# Xonik_Waveshaper_v1_0_w_gp.net
KiCad netlist of a schematic drawn in EAGLE
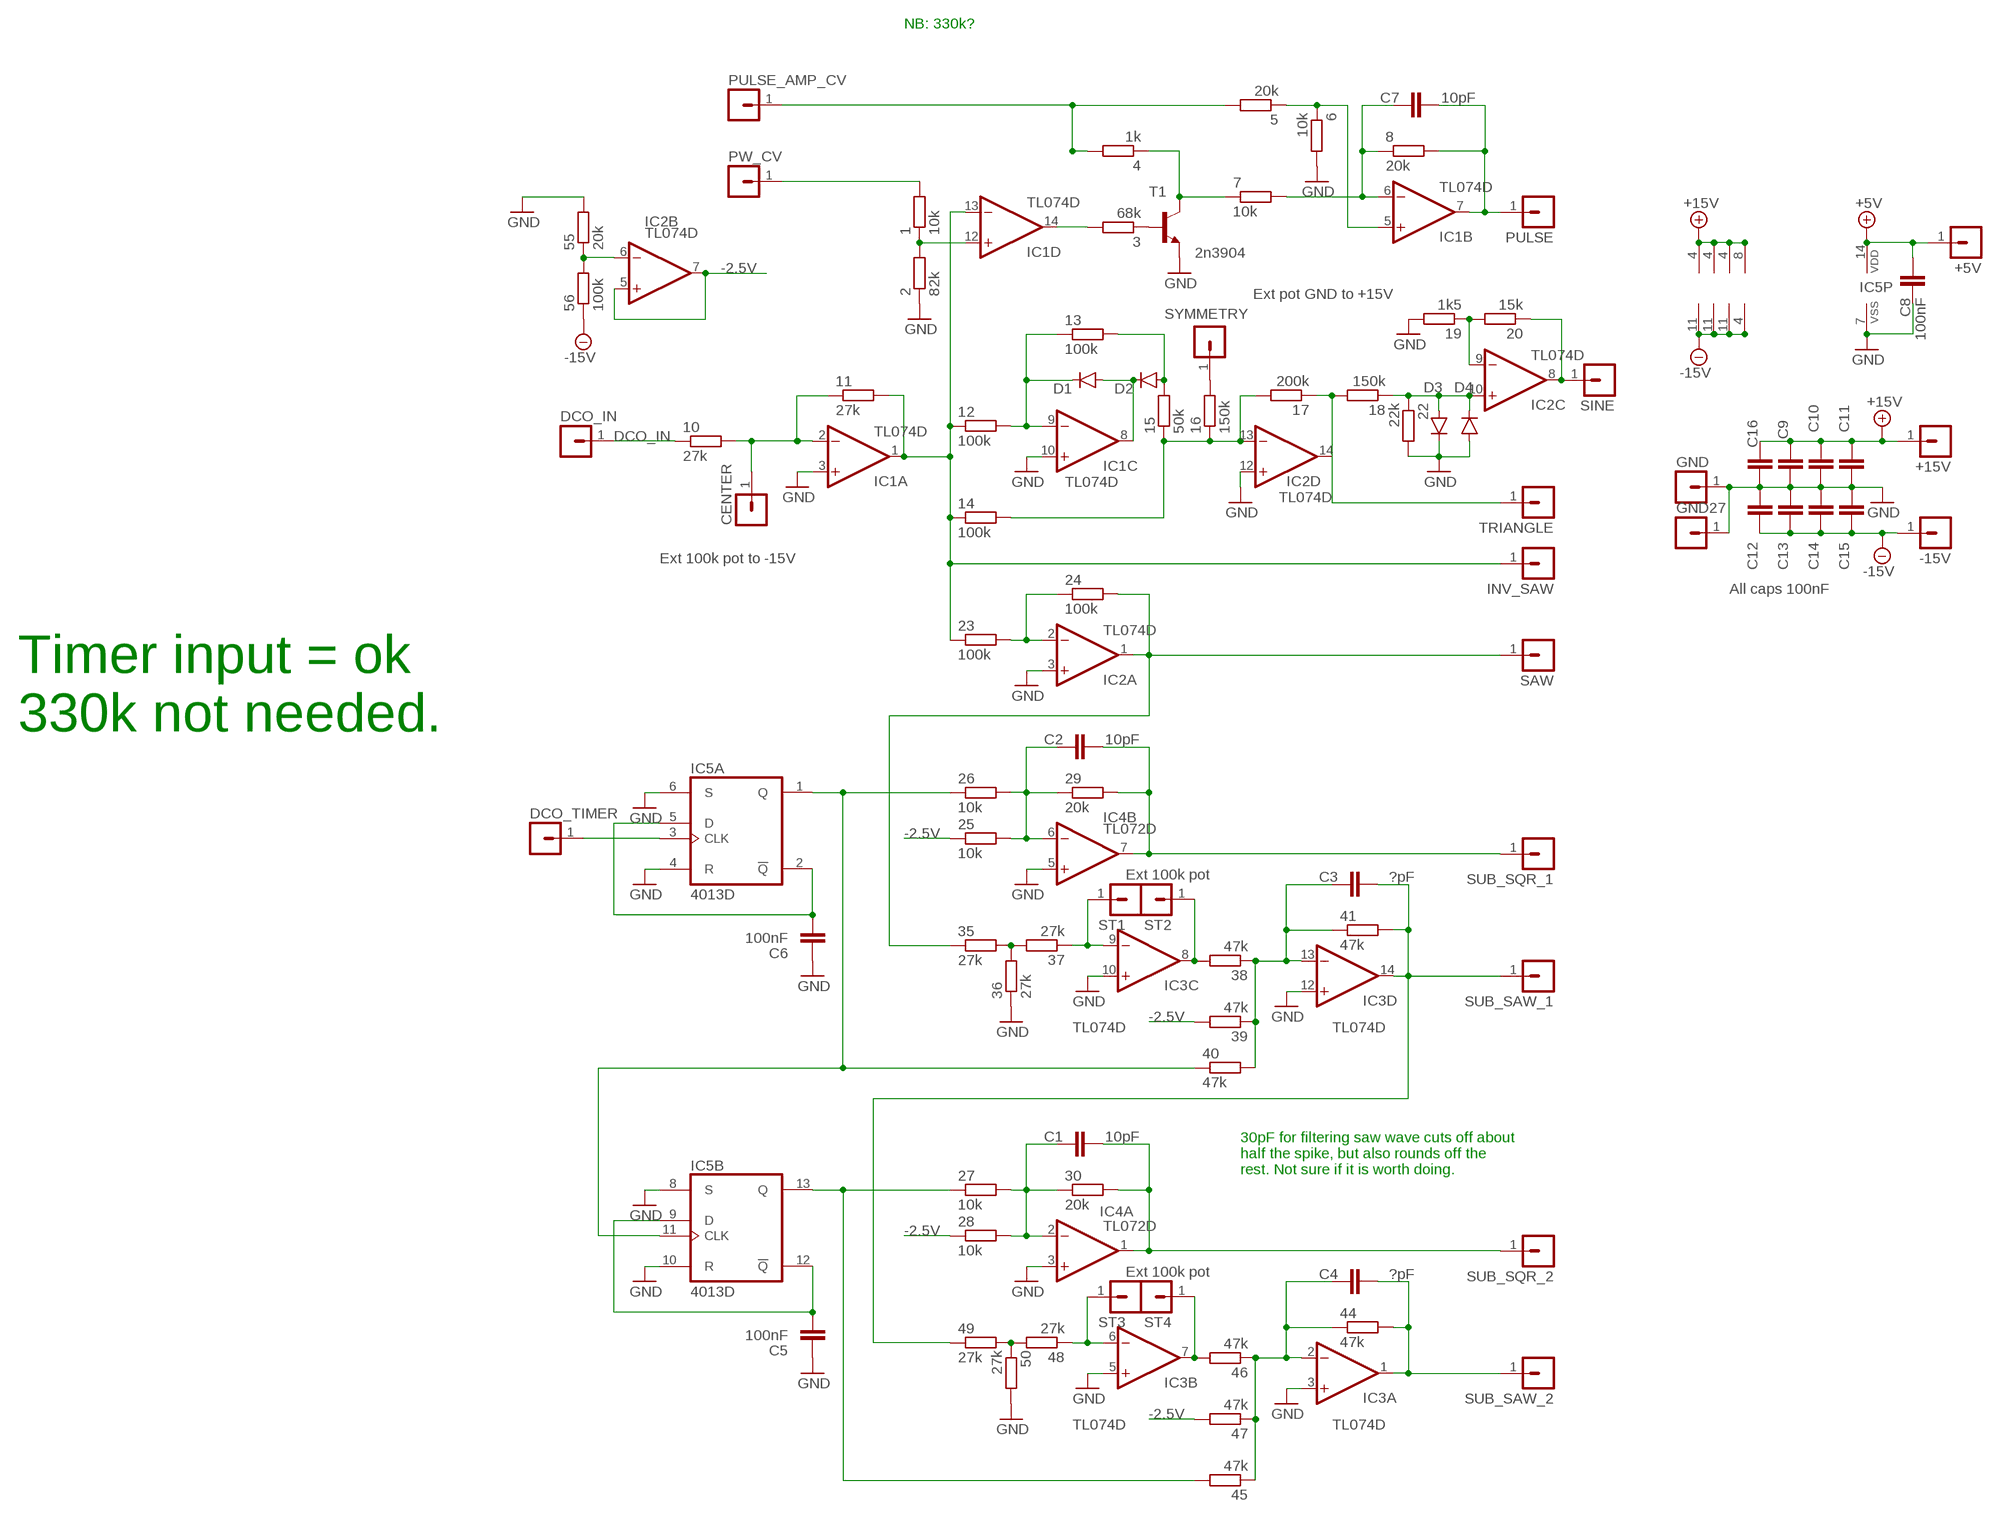
[diagram p0: schematic, sheet 1]

(export (version "E")
  (design (tool "Eeschema 10.0.6"))
  (components
    (comp (ref "+5V")
      (value "MA01-1JP")
      (footprint "eagle-import:SIP-PIN01-1J")
      (libsource (lib "eagle-import") (part "MA01-1JP"))
    )
    (comp (ref "+15V")
      (value "MA01-1JP")
      (footprint "eagle-import:SIP-PIN01-1J")
      (libsource (lib "eagle-import") (part "MA01-1JP"))
    )
    (comp (ref "-15V")
      (value "MA01-1JP")
      (footprint "eagle-import:SIP-PIN01-1J")
      (libsource (lib "eagle-import") (part "MA01-1JP"))
    )
    (comp (ref "1")
      (value "10k")
      (footprint "eagle-import:R0805")
      (libsource (lib "eagle-import") (part "R-EU_R0805"))
    )
    (comp (ref "2")
      (value "82k")
      (footprint "eagle-import:R0805")
      (libsource (lib "eagle-import") (part "R-EU_R0805"))
    )
    (comp (ref "3")
      (value "68k")
      (footprint "eagle-import:R0805")
      (libsource (lib "eagle-import") (part "R-EU_R0805"))
    )
    (comp (ref "4")
      (value "1k")
      (footprint "eagle-import:R0805")
      (libsource (lib "eagle-import") (part "R-EU_R0805"))
    )
    (comp (ref "5")
      (value "20k")
      (footprint "eagle-import:R0805")
      (libsource (lib "eagle-import") (part "R-EU_R0805"))
    )
    (comp (ref "6")
      (value "10k")
      (footprint "eagle-import:R0805")
      (libsource (lib "eagle-import") (part "R-EU_R0805"))
    )
    (comp (ref "7")
      (value "10k")
      (footprint "eagle-import:R0805")
      (libsource (lib "eagle-import") (part "R-EU_R0805"))
    )
    (comp (ref "8")
      (value "20k")
      (footprint "eagle-import:R0805")
      (libsource (lib "eagle-import") (part "R-EU_R0805"))
    )
    (comp (ref "10")
      (value "27k")
      (footprint "eagle-import:R0805")
      (libsource (lib "eagle-import") (part "R-EU_R0805"))
    )
    (comp (ref "11")
      (value "27k")
      (footprint "eagle-import:R0805")
      (libsource (lib "eagle-import") (part "R-EU_R0805"))
    )
    (comp (ref "12")
      (value "100k")
      (footprint "eagle-import:R0805")
      (libsource (lib "eagle-import") (part "R-EU_R0805"))
    )
    (comp (ref "13")
      (value "100k")
      (footprint "eagle-import:R0805")
      (libsource (lib "eagle-import") (part "R-EU_R0805"))
    )
    (comp (ref "14")
      (value "100k")
      (footprint "eagle-import:R0805")
      (libsource (lib "eagle-import") (part "R-EU_R0805"))
    )
    (comp (ref "15")
      (value "50k")
      (footprint "eagle-import:R0805")
      (libsource (lib "eagle-import") (part "R-EU_R0805"))
    )
    (comp (ref "16")
      (value "150k")
      (footprint "eagle-import:R0805")
      (libsource (lib "eagle-import") (part "R-EU_R0805"))
    )
    (comp (ref "17")
      (value "200k")
      (footprint "eagle-import:R0805")
      (libsource (lib "eagle-import") (part "R-EU_R0805"))
    )
    (comp (ref "18")
      (value "150k")
      (footprint "eagle-import:R0805")
      (libsource (lib "eagle-import") (part "R-EU_R0805"))
    )
    (comp (ref "19")
      (value "1k5")
      (footprint "eagle-import:R0805")
      (libsource (lib "eagle-import") (part "R-EU_R0805"))
    )
    (comp (ref "20")
      (value "15k")
      (footprint "eagle-import:R0805")
      (libsource (lib "eagle-import") (part "R-EU_R0805"))
    )
    (comp (ref "22")
      (value "22k")
      (footprint "eagle-import:R0805")
      (libsource (lib "eagle-import") (part "R-EU_R0805"))
    )
    (comp (ref "23")
      (value "100k")
      (footprint "eagle-import:R0805")
      (libsource (lib "eagle-import") (part "R-EU_R0805"))
    )
    (comp (ref "24")
      (value "100k")
      (footprint "eagle-import:R0805")
      (libsource (lib "eagle-import") (part "R-EU_R0805"))
    )
    (comp (ref "25")
      (value "10k")
      (footprint "eagle-import:R0805")
      (libsource (lib "eagle-import") (part "R-EU_R0805"))
    )
    (comp (ref "26")
      (value "10k")
      (footprint "eagle-import:R0805")
      (libsource (lib "eagle-import") (part "R-EU_R0805"))
    )
    (comp (ref "27")
      (value "10k")
      (footprint "eagle-import:R0805")
      (libsource (lib "eagle-import") (part "R-EU_R0805"))
    )
    (comp (ref "28")
      (value "10k")
      (footprint "eagle-import:R0805")
      (libsource (lib "eagle-import") (part "R-EU_R0805"))
    )
    (comp (ref "29")
      (value "20k")
      (footprint "eagle-import:R0805")
      (libsource (lib "eagle-import") (part "R-EU_R0805"))
    )
    (comp (ref "30")
      (value "20k")
      (footprint "eagle-import:R0805")
      (libsource (lib "eagle-import") (part "R-EU_R0805"))
    )
    (comp (ref "35")
      (value "27k")
      (footprint "eagle-import:R0805")
      (libsource (lib "eagle-import") (part "R-EU_R0805"))
    )
    (comp (ref "36")
      (value "27k")
      (footprint "eagle-import:R0805")
      (libsource (lib "eagle-import") (part "R-EU_R0805"))
    )
    (comp (ref "37")
      (value "27k")
      (footprint "eagle-import:R0805")
      (libsource (lib "eagle-import") (part "R-EU_R0805"))
    )
    (comp (ref "38")
      (value "47k")
      (footprint "eagle-import:R0805")
      (libsource (lib "eagle-import") (part "R-EU_R0805"))
    )
    (comp (ref "39")
      (value "47k")
      (footprint "eagle-import:R0805")
      (libsource (lib "eagle-import") (part "R-EU_R0805"))
    )
    (comp (ref "40")
      (value "47k")
      (footprint "eagle-import:R0805")
      (libsource (lib "eagle-import") (part "R-EU_R0805"))
    )
    (comp (ref "41")
      (value "47k")
      (footprint "eagle-import:R0805")
      (libsource (lib "eagle-import") (part "R-EU_R0805"))
    )
    (comp (ref "44")
      (value "47k")
      (footprint "eagle-import:R0805")
      (libsource (lib "eagle-import") (part "R-EU_R0805"))
    )
    (comp (ref "45")
      (value "47k")
      (footprint "eagle-import:R0805")
      (libsource (lib "eagle-import") (part "R-EU_R0805"))
    )
    (comp (ref "46")
      (value "47k")
      (footprint "eagle-import:R0805")
      (libsource (lib "eagle-import") (part "R-EU_R0805"))
    )
    (comp (ref "47")
      (value "47k")
      (footprint "eagle-import:R0805")
      (libsource (lib "eagle-import") (part "R-EU_R0805"))
    )
    (comp (ref "48")
      (value "27k")
      (footprint "eagle-import:R0805")
      (libsource (lib "eagle-import") (part "R-EU_R0805"))
    )
    (comp (ref "49")
      (value "27k")
      (footprint "eagle-import:R0805")
      (libsource (lib "eagle-import") (part "R-EU_R0805"))
    )
    (comp (ref "50")
      (value "27k")
      (footprint "eagle-import:R0805")
      (libsource (lib "eagle-import") (part "R-EU_R0805"))
    )
    (comp (ref "55")
      (value "20k")
      (footprint "eagle-import:R0805")
      (libsource (lib "eagle-import") (part "R-EU_R0805"))
    )
    (comp (ref "56")
      (value "100k")
      (footprint "eagle-import:R0805")
      (libsource (lib "eagle-import") (part "R-EU_R0805"))
    )
    (comp (ref "C1")
      (value "10pF")
      (footprint "eagle-import:C0805")
      (libsource (lib "eagle-import") (part "C-EUC0805"))
    )
    (comp (ref "C2")
      (value "10pF")
      (footprint "eagle-import:C0805")
      (libsource (lib "eagle-import") (part "C-EUC0805"))
    )
    (comp (ref "C3")
      (value "?pF")
      (footprint "eagle-import:C0805")
      (libsource (lib "eagle-import") (part "C-EUC0805"))
    )
    (comp (ref "C4")
      (value "?pF")
      (footprint "eagle-import:C0805")
      (libsource (lib "eagle-import") (part "C-EUC0805"))
    )
    (comp (ref "C5")
      (value "100nF")
      (footprint "eagle-import:C0805")
      (libsource (lib "eagle-import") (part "C-EUC0805"))
    )
    (comp (ref "C6")
      (value "100nF")
      (footprint "eagle-import:C0805")
      (libsource (lib "eagle-import") (part "C-EUC0805"))
    )
    (comp (ref "C7")
      (value "10pF")
      (footprint "eagle-import:C0805")
      (libsource (lib "eagle-import") (part "C-EUC0805"))
    )
    (comp (ref "C8")
      (value "100nF")
      (footprint "eagle-import:C0805")
      (libsource (lib "eagle-import") (part "C-EUC0805"))
    )
    (comp (ref "C9")
      (value "100nF")
      (footprint "eagle-import:C0603K")
      (libsource (lib "eagle-import") (part "C-EUC0603K"))
    )
    (comp (ref "C10")
      (value "100nF")
      (footprint "eagle-import:C0603K")
      (libsource (lib "eagle-import") (part "C-EUC0603K"))
    )
    (comp (ref "C11")
      (value "100nF")
      (footprint "eagle-import:C0603K")
      (libsource (lib "eagle-import") (part "C-EUC0603K"))
    )
    (comp (ref "C12")
      (value "100nF")
      (footprint "eagle-import:C0603K")
      (libsource (lib "eagle-import") (part "C-EUC0603K"))
    )
    (comp (ref "C13")
      (value "100nF")
      (footprint "eagle-import:C0603K")
      (libsource (lib "eagle-import") (part "C-EUC0603K"))
    )
    (comp (ref "C14")
      (value "100nF")
      (footprint "eagle-import:C0603K")
      (libsource (lib "eagle-import") (part "C-EUC0603K"))
    )
    (comp (ref "C15")
      (value "100nF")
      (footprint "eagle-import:C0603K")
      (libsource (lib "eagle-import") (part "C-EUC0603K"))
    )
    (comp (ref "C16")
      (value "100nF")
      (footprint "eagle-import:C0603K")
      (libsource (lib "eagle-import") (part "C-EUC0603K"))
    )
    (comp (ref "CENTER")
      (value "MA01-1JP")
      (footprint "eagle-import:SIP-PIN01-1J")
      (libsource (lib "eagle-import") (part "MA01-1JP"))
    )
    (comp (ref "D1")
      (value "1N41480805")
      (footprint "eagle-import:D0805-J")
      (libsource (lib "eagle-import") (part "1N41480805"))
    )
    (comp (ref "D2")
      (value "1N41480805")
      (footprint "eagle-import:D0805-J")
      (libsource (lib "eagle-import") (part "1N41480805"))
    )
    (comp (ref "D3")
      (value "1N41480805")
      (footprint "eagle-import:D0805-J")
      (libsource (lib "eagle-import") (part "1N41480805"))
    )
    (comp (ref "D4")
      (value "1N41480805")
      (footprint "eagle-import:D0805-J")
      (libsource (lib "eagle-import") (part "1N41480805"))
    )
    (comp (ref "DCO_IN")
      (value "MA01-1JP")
      (footprint "eagle-import:SIP-PIN01-1J")
      (libsource (lib "eagle-import") (part "MA01-1JP"))
    )
    (comp (ref "DCO_TIMER")
      (value "MA01-1JP")
      (footprint "eagle-import:SIP-PIN01-1J")
      (libsource (lib "eagle-import") (part "MA01-1JP"))
    )
    (comp (ref "GND")
      (value "MA01-1JP")
      (footprint "eagle-import:SIP-PIN01-1J")
      (libsource (lib "eagle-import") (part "MA01-1JP"))
    )
    (comp (ref "GND27")
      (value "MA01-1JP")
      (footprint "eagle-import:SIP-PIN01-1J")
      (libsource (lib "eagle-import") (part "MA01-1JP"))
    )
    (comp (ref "IC1")
      (value "TL074D")
      (footprint "eagle-import:SO14")
      (libsource (lib "eagle-import") (part "TL074D"))
    )
    (comp (ref "IC2")
      (value "TL074D")
      (footprint "eagle-import:SO14")
      (libsource (lib "eagle-import") (part "TL074D"))
    )
    (comp (ref "IC3")
      (value "TL074D")
      (footprint "eagle-import:SO14")
      (libsource (lib "eagle-import") (part "TL074D"))
    )
    (comp (ref "IC4")
      (value "TL072D")
      (footprint "eagle-import:SO08J")
      (libsource (lib "eagle-import") (part "TL072D"))
    )
    (comp (ref "IC5")
      (value "4013D")
      (footprint "eagle-import:SO14J")
      (libsource (lib "eagle-import") (part "4013D"))
    )
    (comp (ref "INV_SAW")
      (value "MA01-1JP")
      (footprint "eagle-import:SIP-PIN01-1J")
      (libsource (lib "eagle-import") (part "MA01-1JP"))
    )
    (comp (ref "PULSE")
      (value "MA01-1JP")
      (footprint "eagle-import:SIP-PIN01-1J")
      (libsource (lib "eagle-import") (part "MA01-1JP"))
    )
    (comp (ref "PULSE_AMP_CV")
      (value "MA01-1JP")
      (footprint "eagle-import:SIP-PIN01-1J")
      (libsource (lib "eagle-import") (part "MA01-1JP"))
    )
    (comp (ref "PW_CV")
      (value "MA01-1JP")
      (footprint "eagle-import:SIP-PIN01-1J")
      (libsource (lib "eagle-import") (part "MA01-1JP"))
    )
    (comp (ref "SAW")
      (value "MA01-1JP")
      (footprint "eagle-import:SIP-PIN01-1J")
      (libsource (lib "eagle-import") (part "MA01-1JP"))
    )
    (comp (ref "SINE")
      (value "MA01-1JP")
      (footprint "eagle-import:SIP-PIN01-1J")
      (libsource (lib "eagle-import") (part "MA01-1JP"))
    )
    (comp (ref "ST1")
      (value "MA01-1JP")
      (footprint "eagle-import:SIP-PIN01-1J")
      (libsource (lib "eagle-import") (part "MA01-1JP"))
    )
    (comp (ref "ST2")
      (value "MA01-1JP")
      (footprint "eagle-import:SIP-PIN01-1J")
      (libsource (lib "eagle-import") (part "MA01-1JP"))
    )
    (comp (ref "ST3")
      (value "MA01-1JP")
      (footprint "eagle-import:SIP-PIN01-1J")
      (libsource (lib "eagle-import") (part "MA01-1JP"))
    )
    (comp (ref "ST4")
      (value "MA01-1JP")
      (footprint "eagle-import:SIP-PIN01-1J")
      (libsource (lib "eagle-import") (part "MA01-1JP"))
    )
    (comp (ref "SUB_SAW_1")
      (value "MA01-1JP")
      (footprint "eagle-import:SIP-PIN01-1J")
      (libsource (lib "eagle-import") (part "MA01-1JP"))
    )
    (comp (ref "SUB_SAW_2")
      (value "MA01-1JP")
      (footprint "eagle-import:SIP-PIN01-1J")
      (libsource (lib "eagle-import") (part "MA01-1JP"))
    )
    (comp (ref "SUB_SQR_1")
      (value "MA01-1JP")
      (footprint "eagle-import:SIP-PIN01-1J")
      (libsource (lib "eagle-import") (part "MA01-1JP"))
    )
    (comp (ref "SUB_SQR_2")
      (value "MA01-1JP")
      (footprint "eagle-import:SIP-PIN01-1J")
      (libsource (lib "eagle-import") (part "MA01-1JP"))
    )
    (comp (ref "SYMMETRY")
      (value "MA01-1JP")
      (footprint "eagle-import:SIP-PIN01-1J")
      (libsource (lib "eagle-import") (part "MA01-1JP"))
    )
    (comp (ref "T1")
      (value "2n3904")
      (footprint "eagle-import:SOT23-BEC")
      (libsource (lib "eagle-import") (part "-NPN-SOT23-BECMMBT3904LT1"))
    )
    (comp (ref "TRIANGLE")
      (value "MA01-1JP")
      (footprint "eagle-import:SIP-PIN01-1J")
      (libsource (lib "eagle-import") (part "MA01-1JP"))
    )
  )
  (nets
    (net (code "1") (name "+5V") (class "Default")
      (node (ref "+5V") (pin "1") (pinfunction "1_1") (pintype "passive"))
      (node (ref "C8") (pin "2") (pinfunction "2_2") (pintype "passive"))
      (node (ref "IC5") (pin "14") (pinfunction "VDD_14") (pintype "power_in"))
    )
    (net (code "2") (name "+15V") (class "Default")
      (node (ref "+15V") (pin "1") (pinfunction "1_1") (pintype "passive"))
      (node (ref "C10") (pin "2") (pinfunction "2_2") (pintype "passive"))
      (node (ref "C11") (pin "2") (pinfunction "2_2") (pintype "passive"))
      (node (ref "C16") (pin "2") (pinfunction "2_2") (pintype "passive"))
      (node (ref "C9") (pin "2") (pinfunction "2_2") (pintype "passive"))
      (node (ref "IC1") (pin "4") (pinfunction "V+_4") (pintype "power_in"))
      (node (ref "IC2") (pin "4") (pinfunction "V+_4") (pintype "power_in"))
      (node (ref "IC3") (pin "4") (pinfunction "V+_4") (pintype "power_in"))
      (node (ref "IC4") (pin "8") (pinfunction "V+_8") (pintype "power_in"))
    )
    (net (code "3") (name "-15V") (class "Default")
      (node (ref "-15V") (pin "1") (pinfunction "1_1") (pintype "passive"))
      (node (ref "56") (pin "1") (pinfunction "1_1") (pintype "passive"))
      (node (ref "C12") (pin "1") (pinfunction "1_1") (pintype "passive"))
      (node (ref "C13") (pin "1") (pinfunction "1_1") (pintype "passive"))
      (node (ref "C14") (pin "1") (pinfunction "1_1") (pintype "passive"))
      (node (ref "C15") (pin "1") (pinfunction "1_1") (pintype "passive"))
      (node (ref "IC1") (pin "11") (pinfunction "V-_11") (pintype "power_in"))
      (node (ref "IC2") (pin "11") (pinfunction "V-_11") (pintype "power_in"))
      (node (ref "IC3") (pin "11") (pinfunction "V-_11") (pintype "power_in"))
      (node (ref "IC4") (pin "4") (pinfunction "V-_4") (pintype "power_in"))
    )
    (net (code "4") (name "/-2.5V") (class "Default")
      (node (ref "25") (pin "1") (pinfunction "1_1") (pintype "passive"))
      (node (ref "28") (pin "1") (pinfunction "1_1") (pintype "passive"))
      (node (ref "39") (pin "2") (pinfunction "2_2") (pintype "passive"))
      (node (ref "47") (pin "2") (pinfunction "2_2") (pintype "passive"))
      (node (ref "IC2") (pin "5") (pinfunction "+IN_5") (pintype "input"))
      (node (ref "IC2") (pin "7") (pinfunction "OUT_7") (pintype "output"))
    )
    (net (code "5") (name "/DCO_IN") (class "Default")
      (node (ref "10") (pin "1") (pinfunction "1_1") (pintype "passive"))
      (node (ref "DCO_IN") (pin "1") (pinfunction "1_1") (pintype "passive"))
    )
    (net (code "6") (name "GND") (class "Default")
      (node (ref "19") (pin "2") (pinfunction "2_2") (pintype "passive"))
      (node (ref "2") (pin "1") (pinfunction "1_1") (pintype "passive"))
      (node (ref "22") (pin "2") (pinfunction "2_2") (pintype "passive"))
      (node (ref "36") (pin "1") (pinfunction "1_1") (pintype "passive"))
      (node (ref "50") (pin "2") (pinfunction "2_2") (pintype "passive"))
      (node (ref "55") (pin "2") (pinfunction "2_2") (pintype "passive"))
      (node (ref "6") (pin "2") (pinfunction "2_2") (pintype "passive"))
      (node (ref "C10") (pin "1") (pinfunction "1_1") (pintype "passive"))
      (node (ref "C11") (pin "1") (pinfunction "1_1") (pintype "passive"))
      (node (ref "C12") (pin "2") (pinfunction "2_2") (pintype "passive"))
      (node (ref "C13") (pin "2") (pinfunction "2_2") (pintype "passive"))
      (node (ref "C14") (pin "2") (pinfunction "2_2") (pintype "passive"))
      (node (ref "C15") (pin "2") (pinfunction "2_2") (pintype "passive"))
      (node (ref "C16") (pin "1") (pinfunction "1_1") (pintype "passive"))
      (node (ref "C5") (pin "1") (pinfunction "1_1") (pintype "passive"))
      (node (ref "C6") (pin "1") (pinfunction "1_1") (pintype "passive"))
      (node (ref "C8") (pin "1") (pinfunction "1_1") (pintype "passive"))
      (node (ref "C9") (pin "1") (pinfunction "1_1") (pintype "passive"))
      (node (ref "D3") (pin "C") (pinfunction "C_C") (pintype "passive"))
      (node (ref "D4") (pin "A") (pinfunction "A_A") (pintype "passive"))
      (node (ref "GND") (pin "1") (pinfunction "1_1") (pintype "passive"))
      (node (ref "GND27") (pin "1") (pinfunction "1_1") (pintype "passive"))
      (node (ref "IC1") (pin "10") (pinfunction "+IN_10") (pintype "input"))
      (node (ref "IC1") (pin "3") (pinfunction "+IN_3") (pintype "input"))
      (node (ref "IC2") (pin "12") (pinfunction "+IN_12") (pintype "input"))
      (node (ref "IC2") (pin "3") (pinfunction "+IN_3") (pintype "input"))
      (node (ref "IC3") (pin "10") (pinfunction "+IN_10") (pintype "input"))
      (node (ref "IC3") (pin "12") (pinfunction "+IN_12") (pintype "input"))
      (node (ref "IC3") (pin "3") (pinfunction "+IN_3") (pintype "input"))
      (node (ref "IC3") (pin "5") (pinfunction "+IN_5") (pintype "input"))
      (node (ref "IC4") (pin "3") (pinfunction "+IN_3") (pintype "input"))
      (node (ref "IC4") (pin "5") (pinfunction "+IN_5") (pintype "input"))
      (node (ref "IC5") (pin "10") (pinfunction "R_10") (pintype "input"))
      (node (ref "IC5") (pin "4") (pinfunction "R_4") (pintype "input"))
      (node (ref "IC5") (pin "6") (pinfunction "S_6") (pintype "input"))
      (node (ref "IC5") (pin "7") (pinfunction "VSS_7") (pintype "power_in"))
      (node (ref "IC5") (pin "8") (pinfunction "S_8") (pintype "input"))
      (node (ref "T1") (pin "E") (pinfunction "E_E") (pintype "passive"))
    )
    (net (code "7") (name "Net-(1-Pad2)") (class "Default")
      (node (ref "1") (pin "2") (pinfunction "2_2") (pintype "passive"))
      (node (ref "PW_CV") (pin "1") (pinfunction "1_1") (pintype "passive"))
    )
    (net (code "8") (name "Net-(3-Pad1)") (class "Default")
      (node (ref "3") (pin "1") (pinfunction "1_1") (pintype "passive"))
      (node (ref "T1") (pin "B") (pinfunction "B_B") (pintype "passive"))
    )
    (net (code "9") (name "Net-(4-Pad1)") (class "Default")
      (node (ref "4") (pin "1") (pinfunction "1_1") (pintype "passive"))
      (node (ref "7") (pin "1") (pinfunction "1_1") (pintype "passive"))
      (node (ref "T1") (pin "C") (pinfunction "C_C") (pintype "passive"))
    )
    (net (code "10") (name "Net-(4-Pad2)") (class "Default")
      (node (ref "4") (pin "2") (pinfunction "2_2") (pintype "passive"))
      (node (ref "5") (pin "2") (pinfunction "2_2") (pintype "passive"))
      (node (ref "PULSE_AMP_CV") (pin "1") (pinfunction "1_1") (pintype "passive"))
    )
    (net (code "11") (name "Net-(13-Pad2)") (class "Default")
      (node (ref "13") (pin "2") (pinfunction "2_2") (pintype "passive"))
      (node (ref "15") (pin "2") (pinfunction "2_2") (pintype "passive"))
      (node (ref "D2") (pin "A") (pinfunction "A_A") (pintype "passive"))
    )
    (net (code "12") (name "Net-(16-Pad2)") (class "Default")
      (node (ref "16") (pin "2") (pinfunction "2_2") (pintype "passive"))
      (node (ref "SYMMETRY") (pin "1") (pinfunction "1_1") (pintype "passive"))
    )
    (net (code "13") (name "Net-(35-Pad2)") (class "Default")
      (node (ref "35") (pin "2") (pinfunction "2_2") (pintype "passive"))
      (node (ref "36") (pin "2") (pinfunction "2_2") (pintype "passive"))
      (node (ref "37") (pin "2") (pinfunction "2_2") (pintype "passive"))
    )
    (net (code "14") (name "Net-(48-Pad2)") (class "Default")
      (node (ref "48") (pin "2") (pinfunction "2_2") (pintype "passive"))
      (node (ref "49") (pin "2") (pinfunction "2_2") (pintype "passive"))
      (node (ref "50") (pin "1") (pinfunction "1_1") (pintype "passive"))
    )
    (net (code "15") (name "Net-(IC1A--IN)") (class "Default")
      (node (ref "10") (pin "2") (pinfunction "2_2") (pintype "passive"))
      (node (ref "11") (pin "1") (pinfunction "1_1") (pintype "passive"))
      (node (ref "CENTER") (pin "1") (pinfunction "1_1") (pintype "passive"))
      (node (ref "IC1") (pin "2") (pinfunction "-IN_2") (pintype "input"))
    )
    (net (code "16") (name "Net-(IC1A-OUT)") (class "Default")
      (node (ref "11") (pin "2") (pinfunction "2_2") (pintype "passive"))
      (node (ref "12") (pin "1") (pinfunction "1_1") (pintype "passive"))
      (node (ref "14") (pin "1") (pinfunction "1_1") (pintype "passive"))
      (node (ref "23") (pin "1") (pinfunction "1_1") (pintype "passive"))
      (node (ref "IC1") (pin "1") (pinfunction "OUT_1") (pintype "output"))
      (node (ref "IC1") (pin "13") (pinfunction "-IN_13") (pintype "input"))
      (node (ref "INV_SAW") (pin "1") (pinfunction "1_1") (pintype "passive"))
    )
    (net (code "17") (name "Net-(IC1B-+IN)") (class "Default")
      (node (ref "5") (pin "1") (pinfunction "1_1") (pintype "passive"))
      (node (ref "6") (pin "1") (pinfunction "1_1") (pintype "passive"))
      (node (ref "IC1") (pin "5") (pinfunction "+IN_5") (pintype "input"))
    )
    (net (code "18") (name "Net-(IC1B--IN)") (class "Default")
      (node (ref "7") (pin "2") (pinfunction "2_2") (pintype "passive"))
      (node (ref "8") (pin "1") (pinfunction "1_1") (pintype "passive"))
      (node (ref "C7") (pin "1") (pinfunction "1_1") (pintype "passive"))
      (node (ref "IC1") (pin "6") (pinfunction "-IN_6") (pintype "input"))
    )
    (net (code "19") (name "Net-(IC1B-OUT)") (class "Default")
      (node (ref "8") (pin "2") (pinfunction "2_2") (pintype "passive"))
      (node (ref "C7") (pin "2") (pinfunction "2_2") (pintype "passive"))
      (node (ref "IC1") (pin "7") (pinfunction "OUT_7") (pintype "output"))
      (node (ref "PULSE") (pin "1") (pinfunction "1_1") (pintype "passive"))
    )
    (net (code "20") (name "Net-(IC1C--IN)") (class "Default")
      (node (ref "12") (pin "2") (pinfunction "2_2") (pintype "passive"))
      (node (ref "13") (pin "1") (pinfunction "1_1") (pintype "passive"))
      (node (ref "D1") (pin "C") (pinfunction "C_C") (pintype "passive"))
      (node (ref "IC1") (pin "9") (pinfunction "-IN_9") (pintype "input"))
    )
    (net (code "21") (name "Net-(IC1C-OUT)") (class "Default")
      (node (ref "D1") (pin "A") (pinfunction "A_A") (pintype "passive"))
      (node (ref "D2") (pin "C") (pinfunction "C_C") (pintype "passive"))
      (node (ref "IC1") (pin "8") (pinfunction "OUT_8") (pintype "output"))
    )
    (net (code "22") (name "Net-(IC1D-+IN)") (class "Default")
      (node (ref "1") (pin "1") (pinfunction "1_1") (pintype "passive"))
      (node (ref "2") (pin "2") (pinfunction "2_2") (pintype "passive"))
      (node (ref "IC1") (pin "12") (pinfunction "+IN_12") (pintype "input"))
    )
    (net (code "23") (name "Net-(IC1D-OUT)") (class "Default")
      (node (ref "3") (pin "2") (pinfunction "2_2") (pintype "passive"))
      (node (ref "IC1") (pin "14") (pinfunction "OUT_14") (pintype "output"))
    )
    (net (code "24") (name "Net-(IC2A--IN)") (class "Default")
      (node (ref "23") (pin "2") (pinfunction "2_2") (pintype "passive"))
      (node (ref "24") (pin "1") (pinfunction "1_1") (pintype "passive"))
      (node (ref "IC2") (pin "2") (pinfunction "-IN_2") (pintype "input"))
    )
    (net (code "25") (name "Net-(IC2A-OUT)") (class "Default")
      (node (ref "24") (pin "2") (pinfunction "2_2") (pintype "passive"))
      (node (ref "35") (pin "1") (pinfunction "1_1") (pintype "passive"))
      (node (ref "IC2") (pin "1") (pinfunction "OUT_1") (pintype "output"))
      (node (ref "SAW") (pin "1") (pinfunction "1_1") (pintype "passive"))
    )
    (net (code "26") (name "Net-(IC2B--IN)") (class "Default")
      (node (ref "55") (pin "1") (pinfunction "1_1") (pintype "passive"))
      (node (ref "56") (pin "2") (pinfunction "2_2") (pintype "passive"))
      (node (ref "IC2") (pin "6") (pinfunction "-IN_6") (pintype "input"))
    )
    (net (code "27") (name "Net-(IC2C-+IN)") (class "Default")
      (node (ref "18") (pin "1") (pinfunction "1_1") (pintype "passive"))
      (node (ref "22") (pin "1") (pinfunction "1_1") (pintype "passive"))
      (node (ref "D3") (pin "A") (pinfunction "A_A") (pintype "passive"))
      (node (ref "D4") (pin "C") (pinfunction "C_C") (pintype "passive"))
      (node (ref "IC2") (pin "10") (pinfunction "+IN_10") (pintype "input"))
    )
    (net (code "28") (name "Net-(IC2C--IN)") (class "Default")
      (node (ref "19") (pin "1") (pinfunction "1_1") (pintype "passive"))
      (node (ref "20") (pin "2") (pinfunction "2_2") (pintype "passive"))
      (node (ref "IC2") (pin "9") (pinfunction "-IN_9") (pintype "input"))
    )
    (net (code "29") (name "Net-(IC2C-OUT)") (class "Default")
      (node (ref "20") (pin "1") (pinfunction "1_1") (pintype "passive"))
      (node (ref "IC2") (pin "8") (pinfunction "OUT_8") (pintype "output"))
      (node (ref "SINE") (pin "1") (pinfunction "1_1") (pintype "passive"))
    )
    (net (code "30") (name "Net-(IC2D--IN)") (class "Default")
      (node (ref "14") (pin "2") (pinfunction "2_2") (pintype "passive"))
      (node (ref "15") (pin "1") (pinfunction "1_1") (pintype "passive"))
      (node (ref "16") (pin "1") (pinfunction "1_1") (pintype "passive"))
      (node (ref "17") (pin "2") (pinfunction "2_2") (pintype "passive"))
      (node (ref "IC2") (pin "13") (pinfunction "-IN_13") (pintype "input"))
    )
    (net (code "31") (name "Net-(IC2D-OUT)") (class "Default")
      (node (ref "17") (pin "1") (pinfunction "1_1") (pintype "passive"))
      (node (ref "18") (pin "2") (pinfunction "2_2") (pintype "passive"))
      (node (ref "IC2") (pin "14") (pinfunction "OUT_14") (pintype "output"))
      (node (ref "TRIANGLE") (pin "1") (pinfunction "1_1") (pintype "passive"))
    )
    (net (code "32") (name "Net-(IC3A--IN)") (class "Default")
      (node (ref "44") (pin "1") (pinfunction "1_1") (pintype "passive"))
      (node (ref "45") (pin "1") (pinfunction "1_1") (pintype "passive"))
      (node (ref "46") (pin "1") (pinfunction "1_1") (pintype "passive"))
      (node (ref "47") (pin "1") (pinfunction "1_1") (pintype "passive"))
      (node (ref "C4") (pin "1") (pinfunction "1_1") (pintype "passive"))
      (node (ref "IC3") (pin "2") (pinfunction "-IN_2") (pintype "input"))
    )
    (net (code "33") (name "Net-(IC3A-OUT)") (class "Default")
      (node (ref "44") (pin "2") (pinfunction "2_2") (pintype "passive"))
      (node (ref "C4") (pin "2") (pinfunction "2_2") (pintype "passive"))
      (node (ref "IC3") (pin "1") (pinfunction "OUT_1") (pintype "output"))
      (node (ref "SUB_SAW_2") (pin "1") (pinfunction "1_1") (pintype "passive"))
    )
    (net (code "34") (name "Net-(IC3B--IN)") (class "Default")
      (node (ref "48") (pin "1") (pinfunction "1_1") (pintype "passive"))
      (node (ref "IC3") (pin "6") (pinfunction "-IN_6") (pintype "input"))
      (node (ref "ST3") (pin "1") (pinfunction "1_1") (pintype "passive"))
    )
    (net (code "35") (name "Net-(IC3B-OUT)") (class "Default")
      (node (ref "46") (pin "2") (pinfunction "2_2") (pintype "passive"))
      (node (ref "IC3") (pin "7") (pinfunction "OUT_7") (pintype "output"))
      (node (ref "ST4") (pin "1") (pinfunction "1_1") (pintype "passive"))
    )
    (net (code "36") (name "Net-(IC3C--IN)") (class "Default")
      (node (ref "37") (pin "1") (pinfunction "1_1") (pintype "passive"))
      (node (ref "IC3") (pin "9") (pinfunction "-IN_9") (pintype "input"))
      (node (ref "ST1") (pin "1") (pinfunction "1_1") (pintype "passive"))
    )
    (net (code "37") (name "Net-(IC3C-OUT)") (class "Default")
      (node (ref "38") (pin "2") (pinfunction "2_2") (pintype "passive"))
      (node (ref "IC3") (pin "8") (pinfunction "OUT_8") (pintype "output"))
      (node (ref "ST2") (pin "1") (pinfunction "1_1") (pintype "passive"))
    )
    (net (code "38") (name "Net-(IC3D--IN)") (class "Default")
      (node (ref "38") (pin "1") (pinfunction "1_1") (pintype "passive"))
      (node (ref "39") (pin "1") (pinfunction "1_1") (pintype "passive"))
      (node (ref "40") (pin "2") (pinfunction "2_2") (pintype "passive"))
      (node (ref "41") (pin "1") (pinfunction "1_1") (pintype "passive"))
      (node (ref "C3") (pin "1") (pinfunction "1_1") (pintype "passive"))
      (node (ref "IC3") (pin "13") (pinfunction "-IN_13") (pintype "input"))
    )
    (net (code "39") (name "Net-(IC3D-OUT)") (class "Default")
      (node (ref "41") (pin "2") (pinfunction "2_2") (pintype "passive"))
      (node (ref "49") (pin "1") (pinfunction "1_1") (pintype "passive"))
      (node (ref "C3") (pin "2") (pinfunction "2_2") (pintype "passive"))
      (node (ref "IC3") (pin "14") (pinfunction "OUT_14") (pintype "output"))
      (node (ref "SUB_SAW_1") (pin "1") (pinfunction "1_1") (pintype "passive"))
    )
    (net (code "40") (name "Net-(IC4A--IN)") (class "Default")
      (node (ref "27") (pin "2") (pinfunction "2_2") (pintype "passive"))
      (node (ref "28") (pin "2") (pinfunction "2_2") (pintype "passive"))
      (node (ref "30") (pin "1") (pinfunction "1_1") (pintype "passive"))
      (node (ref "C1") (pin "1") (pinfunction "1_1") (pintype "passive"))
      (node (ref "IC4") (pin "2") (pinfunction "-IN_2") (pintype "input"))
    )
    (net (code "41") (name "Net-(IC4A-OUT)") (class "Default")
      (node (ref "30") (pin "2") (pinfunction "2_2") (pintype "passive"))
      (node (ref "C1") (pin "2") (pinfunction "2_2") (pintype "passive"))
      (node (ref "IC4") (pin "1") (pinfunction "OUT_1") (pintype "output"))
      (node (ref "SUB_SQR_2") (pin "1") (pinfunction "1_1") (pintype "passive"))
    )
    (net (code "42") (name "Net-(IC4B--IN)") (class "Default")
      (node (ref "25") (pin "2") (pinfunction "2_2") (pintype "passive"))
      (node (ref "26") (pin "2") (pinfunction "2_2") (pintype "passive"))
      (node (ref "29") (pin "1") (pinfunction "1_1") (pintype "passive"))
      (node (ref "C2") (pin "1") (pinfunction "1_1") (pintype "passive"))
      (node (ref "IC4") (pin "6") (pinfunction "-IN_6") (pintype "input"))
    )
    (net (code "43") (name "Net-(IC4B-OUT)") (class "Default")
      (node (ref "29") (pin "2") (pinfunction "2_2") (pintype "passive"))
      (node (ref "C2") (pin "2") (pinfunction "2_2") (pintype "passive"))
      (node (ref "IC4") (pin "7") (pinfunction "OUT_7") (pintype "output"))
      (node (ref "SUB_SQR_1") (pin "1") (pinfunction "1_1") (pintype "passive"))
    )
    (net (code "44") (name "Net-(IC5A-CLK)") (class "Default")
      (node (ref "DCO_TIMER") (pin "1") (pinfunction "1_1") (pintype "passive"))
      (node (ref "IC5") (pin "3") (pinfunction "CLK_3") (pintype "input"))
    )
    (net (code "45") (name "Net-(IC5A-D)") (class "Default")
      (node (ref "C6") (pin "2") (pinfunction "2_2") (pintype "passive"))
      (node (ref "IC5") (pin "2") (pinfunction "~{Q}_2") (pintype "output"))
      (node (ref "IC5") (pin "5") (pinfunction "D_5") (pintype "input"))
    )
    (net (code "46") (name "Net-(IC5A-Q)") (class "Default")
      (node (ref "26") (pin "1") (pinfunction "1_1") (pintype "passive"))
      (node (ref "40") (pin "1") (pinfunction "1_1") (pintype "passive"))
      (node (ref "IC5") (pin "1") (pinfunction "Q_1") (pintype "output"))
      (node (ref "IC5") (pin "11") (pinfunction "CLK_11") (pintype "input"))
    )
    (net (code "47") (name "Net-(IC5B-D)") (class "Default")
      (node (ref "C5") (pin "2") (pinfunction "2_2") (pintype "passive"))
      (node (ref "IC5") (pin "12") (pinfunction "~{Q}_12") (pintype "output"))
      (node (ref "IC5") (pin "9") (pinfunction "D_9") (pintype "input"))
    )
    (net (code "48") (name "Net-(IC5B-Q)") (class "Default")
      (node (ref "27") (pin "1") (pinfunction "1_1") (pintype "passive"))
      (node (ref "45") (pin "2") (pinfunction "2_2") (pintype "passive"))
      (node (ref "IC5") (pin "13") (pinfunction "Q_13") (pintype "output"))
    )
  )
)
